# NVME.net
KiCad netlist of a schematic drawn in Altium Designer
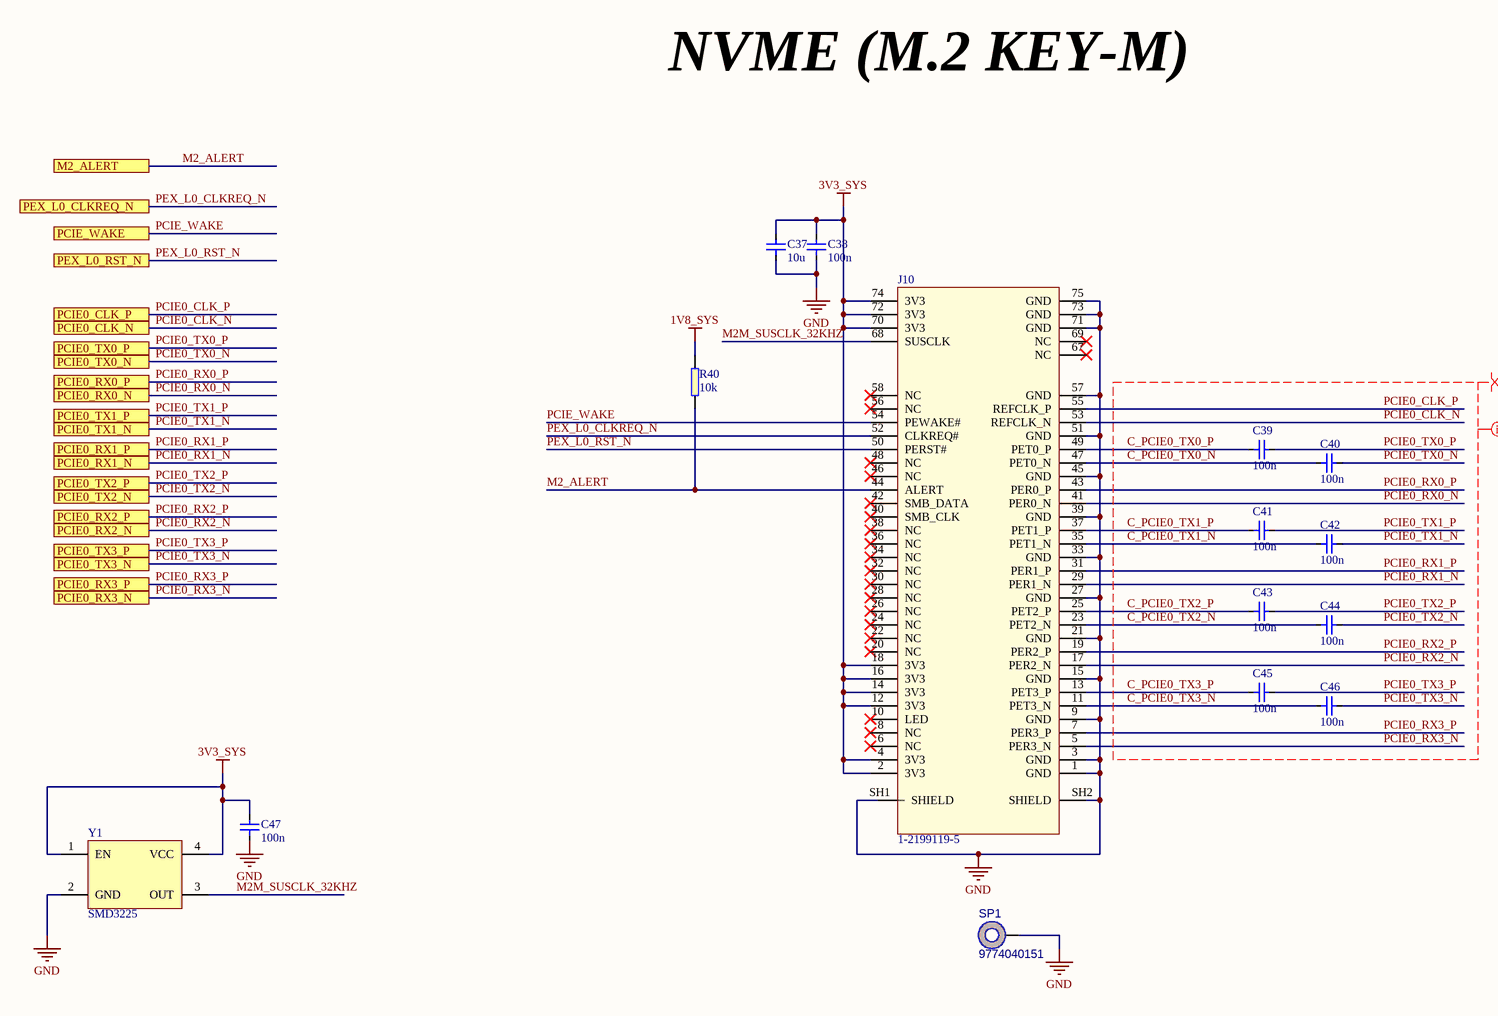
[diagram p0: NVME.SchDoc]

(export (version "E")
  (design (tool "Eeschema 10.0.6"))
  (components
    (comp (ref "C37")
      (value "10u")
      (footprint "C0603")
      (description "MLCC SMT Capacitor 10uF 0603")
      (fields (field (name "PARTNUMBER") "C_10u_0603") (field (name "MANUFACTURER") "Walsin"))
      (libsource (lib "Jetson_Xavier_NX_Carrier_Board_v1.1") (part "C_10u_0603"))
    )
    (comp (ref "C38")
      (value "100n")
      (footprint "C0402")
      (description "MLCC SMT Capacitor 100n 0402")
      (fields (field (name "PARTNUMBER") "C_100n_0402") (field (name "MANUFACTURER") "TDK"))
      (libsource (lib "jetson-nano-baseboard") (part "C_100n_0402"))
    )
    (comp (ref "C39")
      (value "100n")
      (footprint "C0402")
      (description "MLCC SMT Capacitor 100n 0402")
      (fields (field (name "PARTNUMBER") "C_100n_0402") (field (name "MANUFACTURER") "TDK"))
      (libsource (lib "jetson-nano-baseboard") (part "C_100n_0402"))
    )
    (comp (ref "C40")
      (value "100n")
      (footprint "C0402")
      (description "MLCC SMT Capacitor 100n 0402")
      (fields (field (name "PARTNUMBER") "C_100n_0402") (field (name "MANUFACTURER") "TDK"))
      (libsource (lib "jetson-nano-baseboard") (part "C_100n_0402"))
    )
    (comp (ref "C41")
      (value "100n")
      (footprint "C0402")
      (description "MLCC SMT Capacitor 100n 0402")
      (fields (field (name "PARTNUMBER") "C_100n_0402") (field (name "MANUFACTURER") "TDK"))
      (libsource (lib "jetson-nano-baseboard") (part "C_100n_0402"))
    )
    (comp (ref "C42")
      (value "100n")
      (footprint "C0402")
      (description "MLCC SMT Capacitor 100n 0402")
      (fields (field (name "PARTNUMBER") "C_100n_0402") (field (name "MANUFACTURER") "TDK"))
      (libsource (lib "jetson-nano-baseboard") (part "C_100n_0402"))
    )
    (comp (ref "C43")
      (value "100n")
      (footprint "C0402")
      (description "MLCC SMT Capacitor 100n 0402")
      (fields (field (name "PARTNUMBER") "C_100n_0402") (field (name "MANUFACTURER") "TDK"))
      (libsource (lib "jetson-nano-baseboard") (part "C_100n_0402"))
    )
    (comp (ref "C44")
      (value "100n")
      (footprint "C0402")
      (description "MLCC SMT Capacitor 100n 0402")
      (fields (field (name "PARTNUMBER") "C_100n_0402") (field (name "MANUFACTURER") "TDK"))
      (libsource (lib "jetson-nano-baseboard") (part "C_100n_0402"))
    )
    (comp (ref "C45")
      (value "100n")
      (footprint "C0402")
      (description "MLCC SMT Capacitor 100n 0402")
      (fields (field (name "PARTNUMBER") "C_100n_0402") (field (name "MANUFACTURER") "TDK"))
      (libsource (lib "jetson-nano-baseboard") (part "C_100n_0402"))
    )
    (comp (ref "C46")
      (value "100n")
      (footprint "C0402")
      (description "MLCC SMT Capacitor 100n 0402")
      (fields (field (name "PARTNUMBER") "C_100n_0402") (field (name "MANUFACTURER") "TDK"))
      (libsource (lib "jetson-nano-baseboard") (part "C_100n_0402"))
    )
    (comp (ref "C47")
      (value "100n")
      (footprint "C0402")
      (description "MLCC SMT Capacitor 100n 0402")
      (fields (field (name "PARTNUMBER") "C_100n_0402") (field (name "MANUFACTURER") "TDK"))
      (libsource (lib "jetson-nano-baseboard") (part "C_100n_0402"))
    )
    (comp (ref "J10")
      (value "1-2199119-5")
      (footprint "1-2199119-5")
      (description "CONN FEMALE 67POS 0.020 GOLD")
      (fields (field (name "MANUFACTURER") "TE"))
      (libsource (lib "jetson-nano-baseboard") (part "1-2199119-5"))
    )
    (comp (ref "R40")
      (value "10k")
      (footprint "R0402")
      (description "RES, 10k, 0402")
      (fields (field (name "PARTNUMBER") "R_10k_0402") (field (name "MANUFACTURER") "MULTICOMP"))
      (libsource (lib "jetson-nano-baseboard") (part "R_10k_0402"))
    )
    (comp (ref "SP1")
      (value "9774040151")
      (footprint "MEC_STANDOFF_PTH_620C380P")
      (description "RND STANDOFF M2.5X0.45 STEEL 4MM")
      (fields (field (name "MANUFACTURER") "WURTH ELEKTRONIK"))
      (libsource (lib "jetson-nano-baseboard") (part "9774040151"))
    )
    (comp (ref "Y1")
      (value "SMD3225")
      (footprint "XTAL_SMD_4_032X025_D")
      (libsource (lib "jetson-nano-baseboard") (part "SMD3225"))
    )
  )
  (nets
    (net (code "1") (name "/C_PCIE0_TX0_N") (class "Default")
      (node (ref "C40") (pin "1") (pinfunction "1_1") (pintype "passive"))
      (node (ref "J10") (pin "47") (pinfunction "PET0_N_47") (pintype "passive"))
    )
    (net (code "2") (name "/C_PCIE0_TX0_P") (class "Default")
      (node (ref "C39") (pin "1") (pinfunction "1_1") (pintype "passive"))
      (node (ref "J10") (pin "49") (pinfunction "PET0_P_49") (pintype "passive"))
    )
    (net (code "3") (name "/C_PCIE0_TX1_N") (class "Default")
      (node (ref "C42") (pin "1") (pinfunction "1_1") (pintype "passive"))
      (node (ref "J10") (pin "35") (pinfunction "PET1_N_35") (pintype "passive"))
    )
    (net (code "4") (name "/C_PCIE0_TX1_P") (class "Default")
      (node (ref "C41") (pin "1") (pinfunction "1_1") (pintype "passive"))
      (node (ref "J10") (pin "37") (pinfunction "PET1_P_37") (pintype "passive"))
    )
    (net (code "5") (name "/C_PCIE0_TX2_N") (class "Default")
      (node (ref "C44") (pin "1") (pinfunction "1_1") (pintype "passive"))
      (node (ref "J10") (pin "23") (pinfunction "PET2_N_23") (pintype "passive"))
    )
    (net (code "6") (name "/C_PCIE0_TX2_P") (class "Default")
      (node (ref "C43") (pin "1") (pinfunction "1_1") (pintype "passive"))
      (node (ref "J10") (pin "25") (pinfunction "PET2_P_25") (pintype "passive"))
    )
    (net (code "7") (name "/C_PCIE0_TX3_N") (class "Default")
      (node (ref "C46") (pin "1") (pinfunction "1_1") (pintype "passive"))
      (node (ref "J10") (pin "11") (pinfunction "PET3_N_11") (pintype "passive"))
    )
    (net (code "8") (name "/C_PCIE0_TX3_P") (class "Default")
      (node (ref "C45") (pin "1") (pinfunction "1_1") (pintype "passive"))
      (node (ref "J10") (pin "13") (pinfunction "PET3_P_13") (pintype "passive"))
    )
    (net (code "9") (name "/M2M_SUSCLK_32KHZ") (class "Default")
      (node (ref "J10") (pin "68") (pinfunction "SUSCLK_68") (pintype "passive"))
      (node (ref "Y1") (pin "3") (pinfunction "OUT_3") (pintype "passive"))
    )
    (net (code "10") (name "/M2_ALERT") (class "Default")
      (node (ref "J10") (pin "44") (pinfunction "ALERT_44") (pintype "passive"))
      (node (ref "R40") (pin "1") (pintype "passive"))
    )
    (net (code "11") (name "/PCIE0_CLK_N") (class "Default")
      (node (ref "J10") (pin "53") (pinfunction "REFCLK_N_53") (pintype "passive"))
    )
    (net (code "12") (name "/PCIE0_CLK_P") (class "Default")
      (node (ref "J10") (pin "55") (pinfunction "REFCLK_P_55") (pintype "passive"))
    )
    (net (code "13") (name "/PCIE0_RX0_N") (class "Default")
      (node (ref "J10") (pin "41") (pinfunction "PER0_N_41") (pintype "passive"))
    )
    (net (code "14") (name "/PCIE0_RX0_P") (class "Default")
      (node (ref "J10") (pin "43") (pinfunction "PER0_P_43") (pintype "passive"))
    )
    (net (code "15") (name "/PCIE0_RX1_N") (class "Default")
      (node (ref "J10") (pin "29") (pinfunction "PER1_N_29") (pintype "passive"))
    )
    (net (code "16") (name "/PCIE0_RX1_P") (class "Default")
      (node (ref "J10") (pin "31") (pinfunction "PER1_P_31") (pintype "passive"))
    )
    (net (code "17") (name "/PCIE0_RX2_N") (class "Default")
      (node (ref "J10") (pin "17") (pinfunction "PER2_N_17") (pintype "passive"))
    )
    (net (code "18") (name "/PCIE0_RX2_P") (class "Default")
      (node (ref "J10") (pin "19") (pinfunction "PER2_P_19") (pintype "passive"))
    )
    (net (code "19") (name "/PCIE0_RX3_N") (class "Default")
      (node (ref "J10") (pin "5") (pinfunction "PER3_N_5") (pintype "passive"))
    )
    (net (code "20") (name "/PCIE0_RX3_P") (class "Default")
      (node (ref "J10") (pin "7") (pinfunction "PER3_P_7") (pintype "passive"))
    )
    (net (code "21") (name "/PCIE0_TX0_N") (class "Default")
      (node (ref "C40") (pin "2") (pinfunction "2_2") (pintype "passive"))
    )
    (net (code "22") (name "/PCIE0_TX0_P") (class "Default")
      (node (ref "C39") (pin "2") (pinfunction "2_2") (pintype "passive"))
    )
    (net (code "23") (name "/PCIE0_TX1_N") (class "Default")
      (node (ref "C42") (pin "2") (pinfunction "2_2") (pintype "passive"))
    )
    (net (code "24") (name "/PCIE0_TX1_P") (class "Default")
      (node (ref "C41") (pin "2") (pinfunction "2_2") (pintype "passive"))
    )
    (net (code "25") (name "/PCIE0_TX2_N") (class "Default")
      (node (ref "C44") (pin "2") (pinfunction "2_2") (pintype "passive"))
    )
    (net (code "26") (name "/PCIE0_TX2_P") (class "Default")
      (node (ref "C43") (pin "2") (pinfunction "2_2") (pintype "passive"))
    )
    (net (code "27") (name "/PCIE0_TX3_N") (class "Default")
      (node (ref "C46") (pin "2") (pinfunction "2_2") (pintype "passive"))
    )
    (net (code "28") (name "/PCIE0_TX3_P") (class "Default")
      (node (ref "C45") (pin "2") (pinfunction "2_2") (pintype "passive"))
    )
    (net (code "29") (name "/PCIE_WAKE") (class "Default")
      (node (ref "J10") (pin "54") (pinfunction "PEWAKE#_54") (pintype "passive"))
    )
    (net (code "30") (name "/PEX_L0_CLKREQ_N") (class "Default")
      (node (ref "J10") (pin "52") (pinfunction "CLKREQ#_52") (pintype "passive"))
    )
    (net (code "31") (name "/PEX_L0_RST_N") (class "Default")
      (node (ref "J10") (pin "50") (pinfunction "PERST#_50") (pintype "passive"))
    )
    (net (code "32") (name "1V8_SYS") (class "Default") (node (ref "R40") (pin "2") (pintype "passive")))
    (net (code "33") (name "3V3_SYS") (class "Default")
      (node (ref "C37") (pin "2") (pinfunction "2_2") (pintype "passive"))
      (node (ref "C38") (pin "2") (pinfunction "2_2") (pintype "passive"))
      (node (ref "C47") (pin "2") (pinfunction "2_2") (pintype "passive"))
      (node (ref "J10") (pin "12") (pinfunction "3V3_12") (pintype "passive"))
      (node (ref "J10") (pin "14") (pinfunction "3V3_14") (pintype "passive"))
      (node (ref "J10") (pin "16") (pinfunction "3V3_16") (pintype "passive"))
      (node (ref "J10") (pin "18") (pinfunction "3V3_18") (pintype "passive"))
      (node (ref "J10") (pin "2") (pinfunction "3V3_2") (pintype "passive"))
      (node (ref "J10") (pin "4") (pinfunction "3V3_4") (pintype "passive"))
      (node (ref "J10") (pin "70") (pinfunction "3V3_70") (pintype "passive"))
      (node (ref "J10") (pin "72") (pinfunction "3V3_72") (pintype "passive"))
      (node (ref "J10") (pin "74") (pinfunction "3V3_74") (pintype "passive"))
      (node (ref "Y1") (pin "1") (pinfunction "EN_1") (pintype "passive"))
      (node (ref "Y1") (pin "4") (pinfunction "VCC_4") (pintype "passive"))
    )
    (net (code "34") (name "GND") (class "Default")
      (node (ref "C37") (pin "1") (pinfunction "1_1") (pintype "passive"))
      (node (ref "C38") (pin "1") (pinfunction "1_1") (pintype "passive"))
      (node (ref "C47") (pin "1") (pinfunction "1_1") (pintype "passive"))
      (node (ref "J10") (pin "1") (pinfunction "GND_1") (pintype "passive"))
      (node (ref "J10") (pin "15") (pinfunction "GND_15") (pintype "passive"))
      (node (ref "J10") (pin "21") (pinfunction "GND_21") (pintype "passive"))
      (node (ref "J10") (pin "27") (pinfunction "GND_27") (pintype "passive"))
      (node (ref "J10") (pin "3") (pinfunction "GND_3") (pintype "passive"))
      (node (ref "J10") (pin "33") (pinfunction "GND_33") (pintype "passive"))
      (node (ref "J10") (pin "39") (pinfunction "GND_39") (pintype "passive"))
      (node (ref "J10") (pin "45") (pinfunction "GND_45") (pintype "passive"))
      (node (ref "J10") (pin "51") (pinfunction "GND_51") (pintype "passive"))
      (node (ref "J10") (pin "57") (pinfunction "GND_57") (pintype "passive"))
      (node (ref "J10") (pin "71") (pinfunction "GND_71") (pintype "passive"))
      (node (ref "J10") (pin "73") (pinfunction "GND_73") (pintype "passive"))
      (node (ref "J10") (pin "75") (pinfunction "GND_75") (pintype "passive"))
      (node (ref "J10") (pin "9") (pinfunction "GND_9") (pintype "passive"))
      (node (ref "J10") (pin "SH1") (pinfunction "SHIELD_SH1") (pintype "passive"))
      (node (ref "J10") (pin "SH2") (pinfunction "SHIELD_SH2") (pintype "passive"))
      (node (ref "SP1") (pin "1") (pinfunction "1_1") (pintype "passive"))
      (node (ref "Y1") (pin "2") (pinfunction "GND_2") (pintype "passive"))
    )
    (net (code "35") (name "unconnected-(J10-LED-Pad10)") (class "Default")
      (node (ref "J10") (pin "10") (pinfunction "LED_10") (pintype "passive+no_connect"))
    )
    (net (code "36") (name "unconnected-(J10-NC-Pad6)") (class "Default")
      (node (ref "J10") (pin "6") (pinfunction "NC_6") (pintype "passive+no_connect"))
    )
    (net (code "37") (name "unconnected-(J10-NC-Pad8)") (class "Default")
      (node (ref "J10") (pin "8") (pinfunction "NC_8") (pintype "passive+no_connect"))
    )
    (net (code "38") (name "unconnected-(J10-NC-Pad20)") (class "Default")
      (node (ref "J10") (pin "20") (pinfunction "NC_20") (pintype "passive+no_connect"))
    )
    (net (code "39") (name "unconnected-(J10-NC-Pad22)") (class "Default")
      (node (ref "J10") (pin "22") (pinfunction "NC_22") (pintype "passive+no_connect"))
    )
    (net (code "40") (name "unconnected-(J10-NC-Pad24)") (class "Default")
      (node (ref "J10") (pin "24") (pinfunction "NC_24") (pintype "passive+no_connect"))
    )
    (net (code "41") (name "unconnected-(J10-NC-Pad26)") (class "Default")
      (node (ref "J10") (pin "26") (pinfunction "NC_26") (pintype "passive+no_connect"))
    )
    (net (code "42") (name "unconnected-(J10-NC-Pad28)") (class "Default")
      (node (ref "J10") (pin "28") (pinfunction "NC_28") (pintype "passive+no_connect"))
    )
    (net (code "43") (name "unconnected-(J10-NC-Pad30)") (class "Default")
      (node (ref "J10") (pin "30") (pinfunction "NC_30") (pintype "passive+no_connect"))
    )
    (net (code "44") (name "unconnected-(J10-NC-Pad32)") (class "Default")
      (node (ref "J10") (pin "32") (pinfunction "NC_32") (pintype "passive+no_connect"))
    )
    (net (code "45") (name "unconnected-(J10-NC-Pad34)") (class "Default")
      (node (ref "J10") (pin "34") (pinfunction "NC_34") (pintype "passive+no_connect"))
    )
    (net (code "46") (name "unconnected-(J10-NC-Pad36)") (class "Default")
      (node (ref "J10") (pin "36") (pinfunction "NC_36") (pintype "passive+no_connect"))
    )
    (net (code "47") (name "unconnected-(J10-NC-Pad38)") (class "Default")
      (node (ref "J10") (pin "38") (pinfunction "NC_38") (pintype "passive+no_connect"))
    )
    (net (code "48") (name "unconnected-(J10-NC-Pad46)") (class "Default")
      (node (ref "J10") (pin "46") (pinfunction "NC_46") (pintype "passive+no_connect"))
    )
    (net (code "49") (name "unconnected-(J10-NC-Pad48)") (class "Default")
      (node (ref "J10") (pin "48") (pinfunction "NC_48") (pintype "passive+no_connect"))
    )
    (net (code "50") (name "unconnected-(J10-NC-Pad56)") (class "Default")
      (node (ref "J10") (pin "56") (pinfunction "NC_56") (pintype "passive+no_connect"))
    )
    (net (code "51") (name "unconnected-(J10-NC-Pad58)") (class "Default")
      (node (ref "J10") (pin "58") (pinfunction "NC_58") (pintype "passive+no_connect"))
    )
    (net (code "52") (name "unconnected-(J10-NC-Pad67)") (class "Default")
      (node (ref "J10") (pin "67") (pinfunction "NC_67") (pintype "passive+no_connect"))
    )
    (net (code "53") (name "unconnected-(J10-NC-Pad69)") (class "Default")
      (node (ref "J10") (pin "69") (pinfunction "NC_69") (pintype "passive+no_connect"))
    )
    (net (code "54") (name "unconnected-(J10-SMB_CLK-Pad40)") (class "Default")
      (node (ref "J10") (pin "40") (pinfunction "SMB_CLK_40") (pintype "passive+no_connect"))
    )
    (net (code "55") (name "unconnected-(J10-SMB_DATA-Pad42)") (class "Default")
      (node (ref "J10") (pin "42") (pinfunction "SMB_DATA_42") (pintype "passive+no_connect"))
    )
  )
)
